# main.net
KiCad netlist of a schematic drawn in Altium Designer
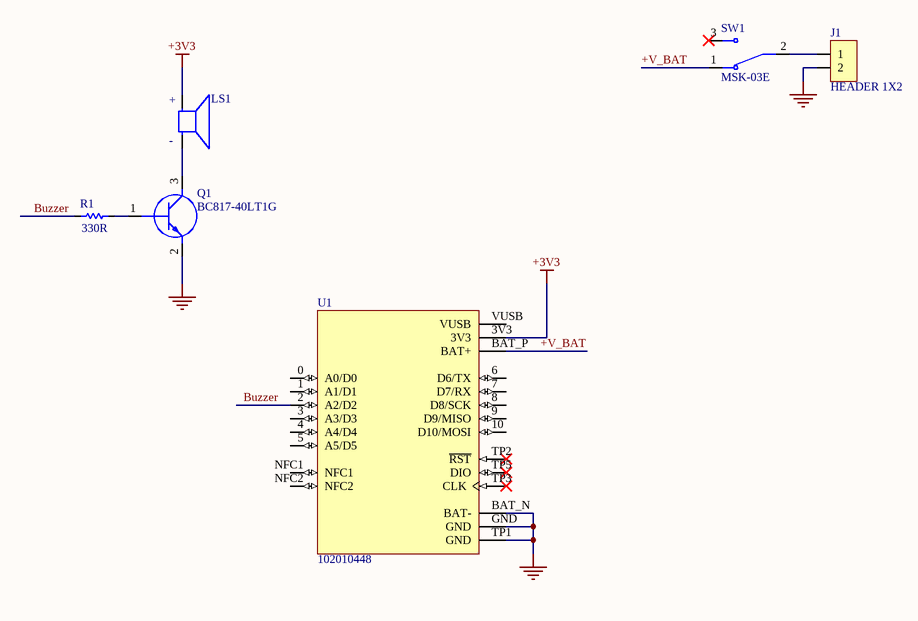
[diagram p0: main.SchDoc]

(export (version "E")
  (design (tool "Eeschema 10.0.6"))
  (components
    (comp (ref "J1")
      (value "HEADER 1X2")
      (footprint "HEADER 1X2")
      (fields (field (name "MANUFATURER PART NUMBER") "HEADER 1X2"))
      (libsource (lib "lib_database_vitor") (part "HEADER 1X2"))
    )
    (comp (ref "LS1")
      (value "BUZZER")
      (footprint "CMT-8504-100-SMT-TR")
      (description "AUDIO INDICATOR 5VDC 30MA 85DB")
      (fields
        (field (name "MF") "{'manufacturer': u'PUI Audio, Inc.'}")
        (field (name "MP") "AI-1223-TWT-3V-2-R")
      )
      (libsource (lib "lib_database_vitor") (part "BUZZER"))
    )
    (comp (ref "Q1")
      (value "BC817-40LT1G")
      (footprint "BC817-40LT1G")
      (description "Transistor BJT NPN")
      (fields
        (field (name "MANUFACTURER_PART_NUMBER") "BC817,215")
        (field (name "MOUSER PART NUMBER") "771-BC817-T/R")
      )
      (libsource (lib "lib_database_vitor") (part "BC817-40LT1G"))
    )
    (comp (ref "R1")
      (value "330R")
      (footprint "RES0603")
      (description "Generic Resistor")
      (fields
        (field (name "MANUFATURER PART NUMBER") "CRCW0603330RJNEA")
        (field (name "MANUFACTURER") "VISHAY DALE")
      )
      (libsource (lib "lib_database_vitor") (part "Resistor"))
    )
    (comp (ref "SW1")
      (value "MSK-03E")
      (footprint "MSK-03E")
      (libsource (lib "lib_database_vitor") (part "MSK-03E"))
    )
    (comp (ref "U1")
      (value "102010448")
      (footprint "102010448")
      (description "- nRF52840 Transceiver; Bluetooth® 5.x Evaluation Board")
      (fields (field (name "MF") "Seeed Technology Co., Ltd"))
      (libsource (lib "lib_database_vitor") (part "102010448"))
    )
  )
  (nets
    (net (code "1") (name "+3V3") (class "Default")
      (node (ref "LS1") (pin "P") (pinfunction "P_P") (pintype "passive"))
      (node (ref "U1") (pin "3V3") (pinfunction "3V3_3V3") (pintype "power_in"))
    )
    (net (code "2") (name "/+V_BAT") (class "Default")
      (node (ref "SW1") (pin "1") (pinfunction "1_1") (pintype "passive"))
      (node (ref "U1") (pin "BAT_P") (pinfunction "BAT+_BAT_P") (pintype "power_in"))
    )
    (net (code "3") (name "/Buzzer") (class "Default")
      (node (ref "R1") (pin "2") (pinfunction "2_2") (pintype "passive"))
      (node (ref "U1") (pin "2") (pinfunction "A2/D2_2") (pintype "bidirectional"))
    )
    (net (code "4") (name "GND") (class "Default")
      (node (ref "J1") (pin "2") (pinfunction "2_2") (pintype "passive"))
      (node (ref "Q1") (pin "2") (pinfunction "E_2") (pintype "passive"))
      (node (ref "U1") (pin "BAT_N") (pinfunction "BAT-_BAT_N") (pintype "power_in"))
      (node (ref "U1") (pin "GND") (pinfunction "GND_GND") (pintype "power_in"))
      (node (ref "U1") (pin "TP1") (pinfunction "GND_TP1") (pintype "power_in"))
    )
    (net (code "5") (name "Net-(J1-Pad1)") (class "Default")
      (node (ref "J1") (pin "1") (pinfunction "1_1") (pintype "passive"))
      (node (ref "SW1") (pin "2") (pinfunction "2_2") (pintype "passive"))
    )
    (net (code "6") (name "Net-(Q1-B)") (class "Default")
      (node (ref "Q1") (pin "1") (pinfunction "B_1") (pintype "passive"))
      (node (ref "R1") (pin "1") (pinfunction "1_1") (pintype "passive"))
    )
    (net (code "7") (name "Net-(Q1-C)") (class "Default")
      (node (ref "LS1") (pin "N") (pinfunction "N_N") (pintype "passive"))
      (node (ref "Q1") (pin "3") (pinfunction "C_3") (pintype "passive"))
    )
    (net (code "8") (name "unconnected-(SW1-Pad3)") (class "Default")
      (node (ref "SW1") (pin "3") (pinfunction "3_3") (pintype "passive+no_connect"))
    )
    (net (code "9") (name "unconnected-(U1-A0{slash}D0-Pad0)") (class "Default")
      (node (ref "U1") (pin "0") (pinfunction "A0/D0_0") (pintype "bidirectional"))
    )
    (net (code "10") (name "unconnected-(U1-A1{slash}D1-Pad1)") (class "Default")
      (node (ref "U1") (pin "1") (pinfunction "A1/D1_1") (pintype "bidirectional"))
    )
    (net (code "11") (name "unconnected-(U1-A3{slash}D3-Pad3)") (class "Default")
      (node (ref "U1") (pin "3") (pinfunction "A3/D3_3") (pintype "bidirectional"))
    )
    (net (code "12") (name "unconnected-(U1-A4{slash}D4-Pad4)") (class "Default")
      (node (ref "U1") (pin "4") (pinfunction "A4/D4_4") (pintype "bidirectional"))
    )
    (net (code "13") (name "unconnected-(U1-A5{slash}D5-Pad5)") (class "Default")
      (node (ref "U1") (pin "5") (pinfunction "A5/D5_5") (pintype "bidirectional"))
    )
    (net (code "14") (name "unconnected-(U1-CLK-PadTP3)") (class "Default")
      (node (ref "U1") (pin "TP3") (pinfunction "CLK_TP3") (pintype "input+no_connect"))
    )
    (net (code "15") (name "unconnected-(U1-D6{slash}TX-Pad6)") (class "Default")
      (node (ref "U1") (pin "6") (pinfunction "D6/TX_6") (pintype "bidirectional"))
    )
    (net (code "16") (name "unconnected-(U1-D7{slash}RX-Pad7)") (class "Default")
      (node (ref "U1") (pin "7") (pinfunction "D7/RX_7") (pintype "bidirectional"))
    )
    (net (code "17") (name "unconnected-(U1-D8{slash}SCK-Pad8)") (class "Default")
      (node (ref "U1") (pin "8") (pinfunction "D8/SCK_8") (pintype "bidirectional"))
    )
    (net (code "18") (name "unconnected-(U1-D9{slash}MISO-Pad9)") (class "Default")
      (node (ref "U1") (pin "9") (pinfunction "D9/MISO_9") (pintype "bidirectional"))
    )
    (net (code "19") (name "unconnected-(U1-D10{slash}MOSI-Pad10)") (class "Default")
      (node (ref "U1") (pin "10") (pinfunction "D10/MOSI_10") (pintype "bidirectional"))
    )
    (net (code "20") (name "unconnected-(U1-DIO-PadTP5)") (class "Default")
      (node (ref "U1") (pin "TP5") (pinfunction "DIO_TP5") (pintype "bidirectional+no_connect"))
    )
    (net (code "21") (name "unconnected-(U1-PadNFC1)") (class "Default")
      (node (ref "U1") (pin "NFC1") (pinfunction "NFC1_NFC1") (pintype "bidirectional"))
    )
    (net (code "22") (name "unconnected-(U1-PadNFC2)") (class "Default")
      (node (ref "U1") (pin "NFC2") (pinfunction "NFC2_NFC2") (pintype "bidirectional"))
    )
    (net (code "23") (name "unconnected-(U1-PadVUSB)") (class "Default")
      (node (ref "U1") (pin "VUSB") (pinfunction "VUSB_VUSB") (pintype "power_in"))
    )
    (net (code "24") (name "unconnected-(U1-~{RST}-PadTP2)") (class "Default")
      (node (ref "U1") (pin "TP2") (pinfunction "~{RST}_TP2") (pintype "input+no_connect"))
    )
  )
)
